# with_solar.net
KiCad netlist of a schematic drawn in EAGLE
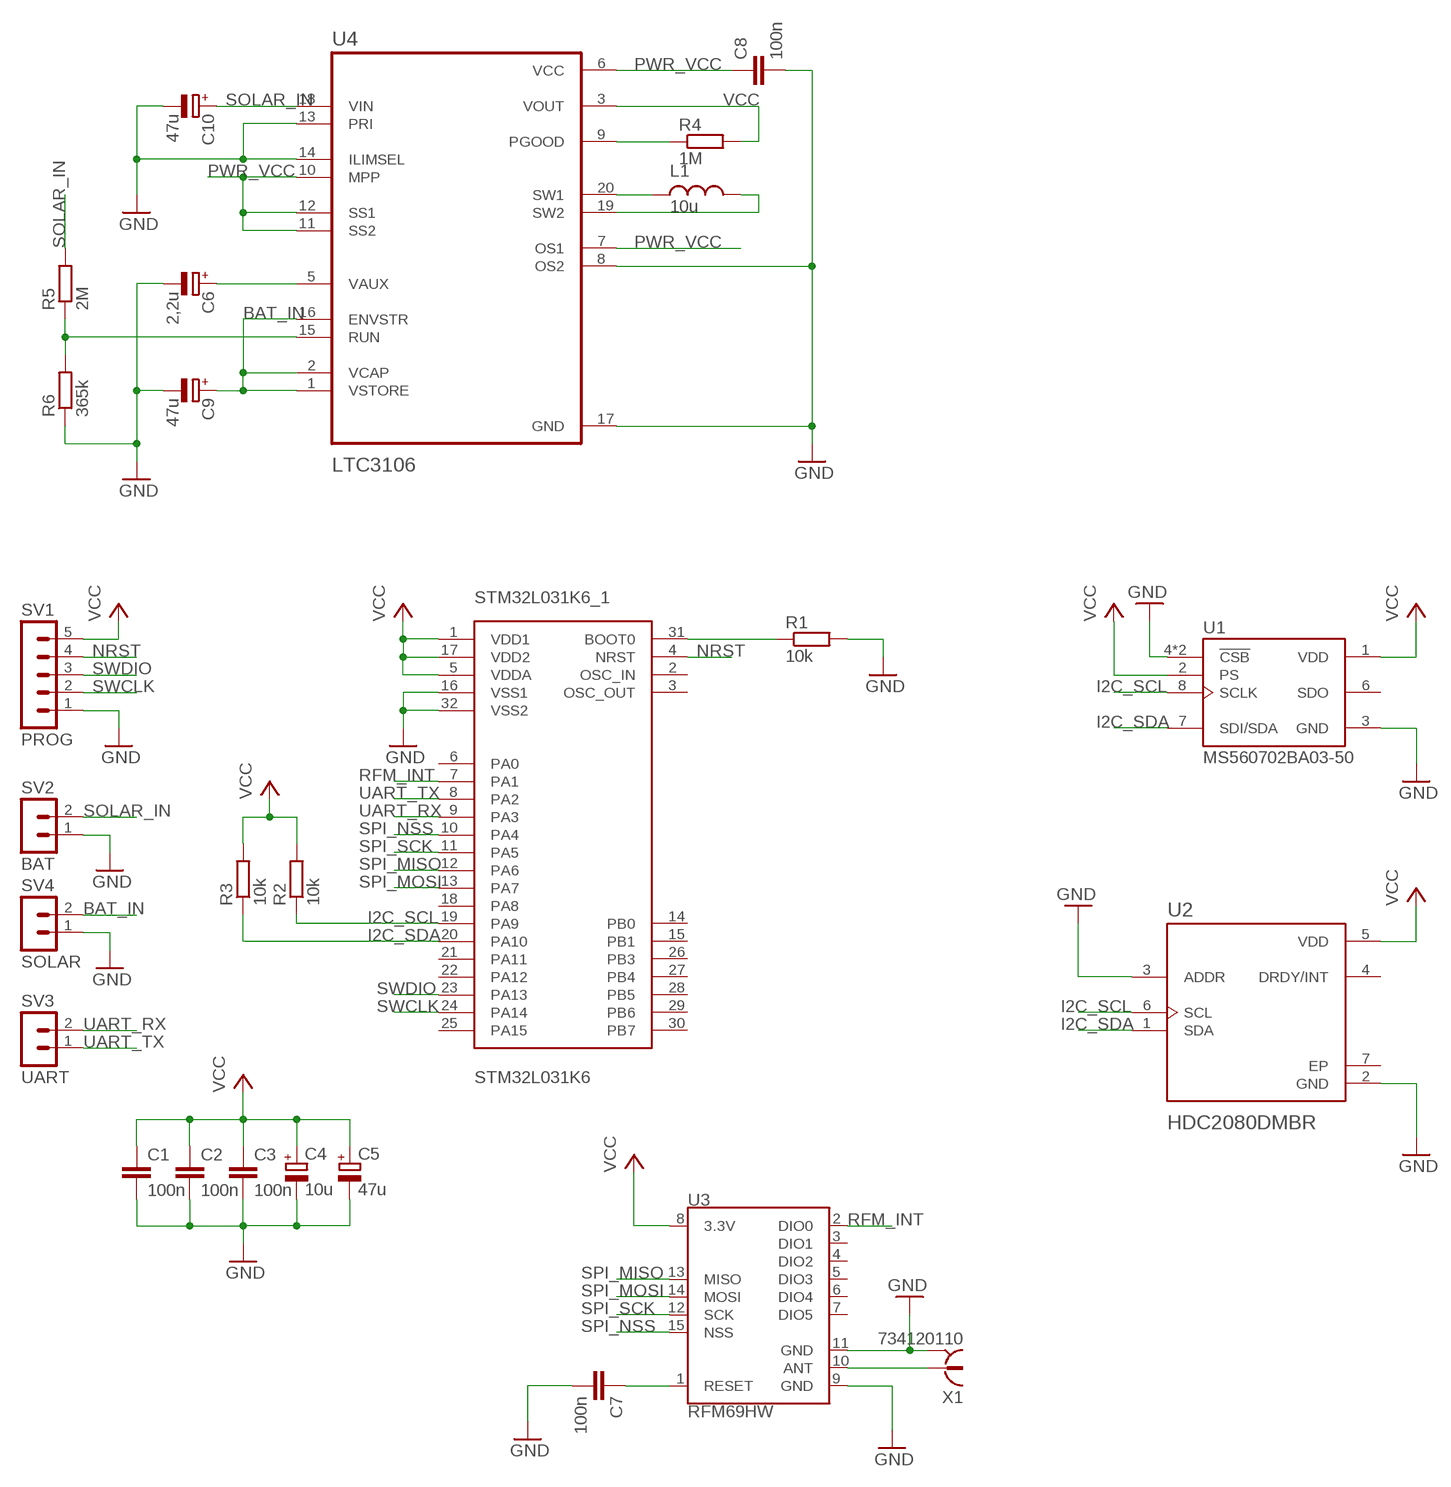
[diagram p0: schematic, sheet 1]

(export (version "E")
  (design (tool "Eeschema 10.0.6"))
  (components
    (comp (ref "C1")
      (value "100n")
      (footprint "eagle-import:C1206")
      (libsource (lib "eagle-import") (part "C-EUC1206"))
    )
    (comp (ref "C2")
      (value "100n")
      (footprint "eagle-import:C1206")
      (libsource (lib "eagle-import") (part "C-EUC1206"))
    )
    (comp (ref "C3")
      (value "100n")
      (footprint "eagle-import:C1206")
      (libsource (lib "eagle-import") (part "C-EUC1206"))
    )
    (comp (ref "C4")
      (value "10u")
      (footprint "eagle-import:UD-4X5,8_NICHICON")
      (libsource (lib "eagle-import") (part "CPOL-EUUD-4X5,8"))
    )
    (comp (ref "C5")
      (value "47u")
      (footprint "eagle-import:UD-4X5,8_NICHICON")
      (libsource (lib "eagle-import") (part "CPOL-EUUD-4X5,8"))
    )
    (comp (ref "C6")
      (value "2,2u")
      (footprint "eagle-import:UD-4X5,8_NICHICON")
      (libsource (lib "eagle-import") (part "CPOL-EUUD-4X5,8"))
    )
    (comp (ref "C7")
      (value "100n")
      (footprint "eagle-import:C1206")
      (libsource (lib "eagle-import") (part "C-EUC1206"))
    )
    (comp (ref "C8")
      (value "100n")
      (footprint "eagle-import:C1206")
      (libsource (lib "eagle-import") (part "C-EUC1206"))
    )
    (comp (ref "C9")
      (value "47u")
      (footprint "eagle-import:UD-4X5,8_NICHICON")
      (libsource (lib "eagle-import") (part "CPOL-EUUD-4X5,8"))
    )
    (comp (ref "C10")
      (value "47u")
      (footprint "eagle-import:UD-4X5,8_NICHICON")
      (libsource (lib "eagle-import") (part "CPOL-EUUD-4X5,8"))
    )
    (comp (ref "L1")
      (value "10u")
      (footprint "eagle-import:R1210")
      (libsource (lib "eagle-import") (part "L1210"))
    )
    (comp (ref "R1")
      (value "10k")
      (footprint "eagle-import:R0805")
      (libsource (lib "eagle-import") (part "R-EU_R0805"))
    )
    (comp (ref "R2")
      (value "10k")
      (footprint "eagle-import:R0805")
      (libsource (lib "eagle-import") (part "R-EU_R0805"))
    )
    (comp (ref "R3")
      (value "10k")
      (footprint "eagle-import:R0805")
      (libsource (lib "eagle-import") (part "R-EU_R0805"))
    )
    (comp (ref "R4")
      (value "1M")
      (footprint "eagle-import:R0805")
      (libsource (lib "eagle-import") (part "R-EU_R0805"))
    )
    (comp (ref "R5")
      (value "2M")
      (footprint "eagle-import:R0805")
      (libsource (lib "eagle-import") (part "R-EU_R0805"))
    )
    (comp (ref "R6")
      (value "365k")
      (footprint "eagle-import:R0805")
      (libsource (lib "eagle-import") (part "R-EU_R0805"))
    )
    (comp (ref "STM32L031K6_1")
      (value "STM32L031K6")
      (footprint "eagle-import:LQFP32-7X7")
      (libsource (lib "eagle-import") (part "STM32L031K6"))
    )
    (comp (ref "SV1")
      (value "PROG")
      (footprint "eagle-import:MA05-1")
      (libsource (lib "eagle-import") (part "MA05-1"))
    )
    (comp (ref "SV2")
      (value "BAT")
      (footprint "eagle-import:MA02-1")
      (libsource (lib "eagle-import") (part "MA02-1"))
    )
    (comp (ref "SV3")
      (value "UART")
      (footprint "eagle-import:MA02-1")
      (libsource (lib "eagle-import") (part "MA02-1"))
    )
    (comp (ref "SV4")
      (value "SOLAR")
      (footprint "eagle-import:MA02-1")
      (libsource (lib "eagle-import") (part "MA02-1"))
    )
    (comp (ref "U1")
      (value "MS560702BA03-50")
      (footprint "eagle-import:SON125P300X500X100-8N")
      (fields (field (name "MF") "TE Connectivity"))
      (libsource (lib "eagle-import") (part "MS560702BA03-50"))
    )
    (comp (ref "U2")
      (value "HDC2080DMBR")
      (footprint "eagle-import:SON100P300X300X80-7N")
      (fields (field (name "MF") "Texas Instruments"))
      (libsource (lib "eagle-import") (part "HDC2080DMBR"))
    )
    (comp (ref "U3")
      (value "RFM69HW")
      (footprint "eagle-import:RFM69W-XXXS2")
      (libsource (lib "eagle-import") (part "RFM69HW"))
    )
    (comp (ref "U4")
      (value "LTC3106")
      (footprint "eagle-import:LTC3106")
      (libsource (lib "eagle-import") (part "LTC3106"))
    )
    (comp (ref "X1")
      (value "734120110")
      (footprint "eagle-import:734120110")
      (libsource (lib "eagle-import") (part "734120110"))
    )
  )
  (nets
    (net (code "1") (name "/BAT_IN") (class "Default")
      (node (ref "C9") (pin "+") (pinfunction "+_+") (pintype "passive"))
      (node (ref "SV4") (pin "2") (pinfunction "3_2") (pintype "passive"))
      (node (ref "U4") (pin "1") (pinfunction "VSTORE_1") (pintype "bidirectional"))
      (node (ref "U4") (pin "16") (pinfunction "ENVSTR_16") (pintype "input"))
      (node (ref "U4") (pin "2") (pinfunction "VCAP_2") (pintype "bidirectional"))
    )
    (net (code "2") (name "/I2C_SCL") (class "Default")
      (node (ref "R2") (pin "1") (pinfunction "1_1") (pintype "passive"))
      (node (ref "STM32L031K6_1") (pin "19") (pinfunction "PA9_19") (pintype "bidirectional"))
      (node (ref "U1") (pin "8") (pinfunction "SCLK_8") (pintype "input"))
      (node (ref "U2") (pin "6") (pinfunction "SCL_6") (pintype "input"))
    )
    (net (code "3") (name "/I2C_SDA") (class "Default")
      (node (ref "R3") (pin "1") (pinfunction "1_1") (pintype "passive"))
      (node (ref "STM32L031K6_1") (pin "20") (pinfunction "PA10_20") (pintype "bidirectional"))
      (node (ref "U1") (pin "7") (pinfunction "SDI/SDA_7") (pintype "bidirectional"))
      (node (ref "U2") (pin "1") (pinfunction "SDA_1") (pintype "bidirectional"))
    )
    (net (code "4") (name "/NRST") (class "Default")
      (node (ref "STM32L031K6_1") (pin "4") (pinfunction "NRST_4") (pintype "bidirectional"))
      (node (ref "SV1") (pin "4") (pinfunction "4_4") (pintype "passive"))
    )
    (net (code "5") (name "/PWR_VCC") (class "Default")
      (node (ref "C8") (pin "1") (pinfunction "1_1") (pintype "passive"))
      (node (ref "U4") (pin "10") (pinfunction "MPP_10") (pintype "input"))
      (node (ref "U4") (pin "11") (pinfunction "SS2_11") (pintype "input"))
      (node (ref "U4") (pin "12") (pinfunction "SS1_12") (pintype "input"))
      (node (ref "U4") (pin "6") (pinfunction "VCC_6") (pintype "power_in"))
      (node (ref "U4") (pin "7") (pinfunction "OS1_7") (pintype "input"))
    )
    (net (code "6") (name "/RFM_INT") (class "Default")
      (node (ref "STM32L031K6_1") (pin "7") (pinfunction "PA1_7") (pintype "bidirectional"))
      (node (ref "U3") (pin "2") (pinfunction "DIO0_2") (pintype "bidirectional"))
    )
    (net (code "7") (name "/SOLAR_IN") (class "Default")
      (node (ref "C10") (pin "+") (pinfunction "+_+") (pintype "passive"))
      (node (ref "R5") (pin "2") (pinfunction "2_2") (pintype "passive"))
      (node (ref "SV2") (pin "2") (pinfunction "3_2") (pintype "passive"))
      (node (ref "U4") (pin "18") (pinfunction "VIN_18") (pintype "input"))
    )
    (net (code "8") (name "/SPI_MISO") (class "Default")
      (node (ref "STM32L031K6_1") (pin "12") (pinfunction "PA6_12") (pintype "bidirectional"))
      (node (ref "U3") (pin "13") (pinfunction "MISO_13") (pintype "bidirectional"))
    )
    (net (code "9") (name "/SPI_MOSI") (class "Default")
      (node (ref "STM32L031K6_1") (pin "13") (pinfunction "PA7_13") (pintype "bidirectional"))
      (node (ref "U3") (pin "14") (pinfunction "MOSI_14") (pintype "input"))
    )
    (net (code "10") (name "/SPI_NSS") (class "Default")
      (node (ref "STM32L031K6_1") (pin "10") (pinfunction "PA4_10") (pintype "bidirectional"))
      (node (ref "U3") (pin "15") (pinfunction "NSS_15") (pintype "input"))
    )
    (net (code "11") (name "/SPI_SCK") (class "Default")
      (node (ref "STM32L031K6_1") (pin "11") (pinfunction "PA5_11") (pintype "bidirectional"))
      (node (ref "U3") (pin "12") (pinfunction "SCK_12") (pintype "input"))
    )
    (net (code "12") (name "/SWCLK") (class "Default")
      (node (ref "STM32L031K6_1") (pin "24") (pinfunction "PA14_24") (pintype "bidirectional"))
      (node (ref "SV1") (pin "2") (pinfunction "2_2") (pintype "passive"))
    )
    (net (code "13") (name "/SWDIO") (class "Default")
      (node (ref "STM32L031K6_1") (pin "23") (pinfunction "PA13_23") (pintype "bidirectional"))
      (node (ref "SV1") (pin "3") (pinfunction "3_3") (pintype "passive"))
    )
    (net (code "14") (name "/UART_RX") (class "Default")
      (node (ref "STM32L031K6_1") (pin "9") (pinfunction "PA3_9") (pintype "bidirectional"))
      (node (ref "SV3") (pin "2") (pinfunction "3_2") (pintype "passive"))
    )
    (net (code "15") (name "/UART_TX") (class "Default")
      (node (ref "STM32L031K6_1") (pin "8") (pinfunction "PA2_8") (pintype "bidirectional"))
      (node (ref "SV3") (pin "1") (pinfunction "2_1") (pintype "passive"))
    )
    (net (code "16") (name "GND") (class "Default")
      (node (ref "C1") (pin "2") (pinfunction "2_2") (pintype "passive"))
      (node (ref "C10") (pin "-") (pinfunction "-_-") (pintype "passive"))
      (node (ref "C2") (pin "2") (pinfunction "2_2") (pintype "passive"))
      (node (ref "C3") (pin "2") (pinfunction "2_2") (pintype "passive"))
      (node (ref "C4") (pin "-") (pinfunction "-_-") (pintype "passive"))
      (node (ref "C5") (pin "-") (pinfunction "-_-") (pintype "passive"))
      (node (ref "C6") (pin "-") (pinfunction "-_-") (pintype "passive"))
      (node (ref "C7") (pin "2") (pinfunction "2_2") (pintype "passive"))
      (node (ref "C8") (pin "2") (pinfunction "2_2") (pintype "passive"))
      (node (ref "C9") (pin "-") (pinfunction "-_-") (pintype "passive"))
      (node (ref "R1") (pin "2") (pinfunction "2_2") (pintype "passive"))
      (node (ref "R6") (pin "1") (pinfunction "1_1") (pintype "passive"))
      (node (ref "STM32L031K6_1") (pin "16") (pinfunction "VSS1_16") (pintype "bidirectional"))
      (node (ref "STM32L031K6_1") (pin "32") (pinfunction "VSS2_32") (pintype "bidirectional"))
      (node (ref "SV1") (pin "1") (pinfunction "1_1") (pintype "passive"))
      (node (ref "SV2") (pin "1") (pinfunction "2_1") (pintype "passive"))
      (node (ref "SV4") (pin "1") (pinfunction "2_1") (pintype "passive"))
      (node (ref "U1") (pin "3") (pinfunction "GND_3") (pintype "power_in"))
      (node (ref "U1") (pin "4") (pinfunction "~{CSB}_4") (pintype "input"))
      (node (ref "U1") (pin "5") (pinfunction "~{CSB}_5") (pintype "input"))
      (node (ref "U2") (pin "2") (pinfunction "GND_2") (pintype "power_in"))
      (node (ref "U2") (pin "3") (pinfunction "ADDR_3") (pintype "input"))
      (node (ref "U3") (pin "11") (pinfunction "GND_11") (pintype "power_in"))
      (node (ref "U3") (pin "9") (pinfunction "GND_9") (pintype "power_in"))
      (node (ref "U4") (pin "13") (pinfunction "PRI_13") (pintype "input"))
      (node (ref "U4") (pin "14") (pinfunction "ILIMSEL_14") (pintype "input"))
      (node (ref "U4") (pin "17") (pinfunction "GND_17") (pintype "power_in"))
      (node (ref "U4") (pin "8") (pinfunction "OS2_8") (pintype "input"))
      (node (ref "X1") (pin "S@1") (pinfunction "2_S@1") (pintype "passive"))
      (node (ref "X1") (pin "S@2") (pinfunction "2_S@2") (pintype "passive"))
      (node (ref "X1") (pin "S@3") (pinfunction "2_S@3") (pintype "passive"))
    )
    (net (code "17") (name "Net-(STM32L031K6_1-BOOT0)") (class "Default")
      (node (ref "R1") (pin "1") (pinfunction "1_1") (pintype "passive"))
      (node (ref "STM32L031K6_1") (pin "31") (pinfunction "BOOT0_31") (pintype "bidirectional"))
    )
    (net (code "18") (name "Net-(U3-ANT)") (class "Default")
      (node (ref "U3") (pin "10") (pinfunction "ANT_10") (pintype "passive"))
      (node (ref "X1") (pin "1") (pinfunction "1_1") (pintype "passive"))
    )
    (net (code "19") (name "Net-(U3-RESET)") (class "Default")
      (node (ref "C7") (pin "1") (pinfunction "1_1") (pintype "passive"))
      (node (ref "U3") (pin "1") (pinfunction "RESET_1") (pintype "input"))
    )
    (net (code "20") (name "Net-(U4-PGOOD)") (class "Default")
      (node (ref "R4") (pin "1") (pinfunction "1_1") (pintype "passive"))
      (node (ref "U4") (pin "9") (pinfunction "PGOOD_9") (pintype "bidirectional"))
    )
    (net (code "21") (name "Net-(U4-RUN)") (class "Default")
      (node (ref "R5") (pin "1") (pinfunction "1_1") (pintype "passive"))
      (node (ref "R6") (pin "2") (pinfunction "2_2") (pintype "passive"))
      (node (ref "U4") (pin "15") (pinfunction "RUN_15") (pintype "input"))
    )
    (net (code "22") (name "Net-(U4-SW1)") (class "Default")
      (node (ref "L1") (pin "1") (pinfunction "1_1") (pintype "passive"))
      (node (ref "U4") (pin "20") (pinfunction "SW1_20") (pintype "bidirectional"))
    )
    (net (code "23") (name "Net-(U4-SW2)") (class "Default")
      (node (ref "L1") (pin "2") (pinfunction "2_2") (pintype "passive"))
      (node (ref "U4") (pin "19") (pinfunction "SW2_19") (pintype "bidirectional"))
    )
    (net (code "24") (name "Net-(U4-VAUX)") (class "Default")
      (node (ref "C6") (pin "+") (pinfunction "+_+") (pintype "passive"))
      (node (ref "U4") (pin "5") (pinfunction "VAUX_5") (pintype "bidirectional"))
    )
    (net (code "25") (name "VCC") (class "Default")
      (node (ref "C1") (pin "1") (pinfunction "1_1") (pintype "passive"))
      (node (ref "C2") (pin "1") (pinfunction "1_1") (pintype "passive"))
      (node (ref "C3") (pin "1") (pinfunction "1_1") (pintype "passive"))
      (node (ref "C4") (pin "+") (pinfunction "+_+") (pintype "passive"))
      (node (ref "C5") (pin "+") (pinfunction "+_+") (pintype "passive"))
      (node (ref "R2") (pin "2") (pinfunction "2_2") (pintype "passive"))
      (node (ref "R3") (pin "2") (pinfunction "2_2") (pintype "passive"))
      (node (ref "R4") (pin "2") (pinfunction "2_2") (pintype "passive"))
      (node (ref "STM32L031K6_1") (pin "1") (pinfunction "VDD1_1") (pintype "bidirectional"))
      (node (ref "STM32L031K6_1") (pin "17") (pinfunction "VDD2_17") (pintype "bidirectional"))
      (node (ref "STM32L031K6_1") (pin "5") (pinfunction "VDDA_5") (pintype "bidirectional"))
      (node (ref "SV1") (pin "5") (pinfunction "5_5") (pintype "passive"))
      (node (ref "U1") (pin "1") (pinfunction "VDD_1") (pintype "power_in"))
      (node (ref "U1") (pin "2") (pinfunction "PS_2") (pintype "input"))
      (node (ref "U2") (pin "5") (pinfunction "VDD_5") (pintype "power_in"))
      (node (ref "U3") (pin "8") (pinfunction "3.3V_8") (pintype "power_in"))
      (node (ref "U4") (pin "3") (pinfunction "VOUT_3") (pintype "output"))
    )
    (net (code "26") (name "unconnected-(STM32L031K6_1-OSC_IN-Pad2)") (class "Default")
      (node (ref "STM32L031K6_1") (pin "2") (pinfunction "OSC_IN_2") (pintype "bidirectional"))
    )
    (net (code "27") (name "unconnected-(STM32L031K6_1-OSC_OUT-Pad3)") (class "Default")
      (node (ref "STM32L031K6_1") (pin "3") (pinfunction "OSC_OUT_3") (pintype "bidirectional"))
    )
    (net (code "28") (name "unconnected-(STM32L031K6_1-PA0-Pad6)") (class "Default")
      (node (ref "STM32L031K6_1") (pin "6") (pinfunction "PA0_6") (pintype "bidirectional"))
    )
    (net (code "29") (name "unconnected-(STM32L031K6_1-PA8-Pad18)") (class "Default")
      (node (ref "STM32L031K6_1") (pin "18") (pinfunction "PA8_18") (pintype "bidirectional"))
    )
    (net (code "30") (name "unconnected-(STM32L031K6_1-PA11-Pad21)") (class "Default")
      (node (ref "STM32L031K6_1") (pin "21") (pinfunction "PA11_21") (pintype "bidirectional"))
    )
    (net (code "31") (name "unconnected-(STM32L031K6_1-PA12-Pad22)") (class "Default")
      (node (ref "STM32L031K6_1") (pin "22") (pinfunction "PA12_22") (pintype "bidirectional"))
    )
    (net (code "32") (name "unconnected-(STM32L031K6_1-PA15-Pad25)") (class "Default")
      (node (ref "STM32L031K6_1") (pin "25") (pinfunction "PA15_25") (pintype "bidirectional"))
    )
    (net (code "33") (name "unconnected-(STM32L031K6_1-PB0-Pad14)") (class "Default")
      (node (ref "STM32L031K6_1") (pin "14") (pinfunction "PB0_14") (pintype "bidirectional"))
    )
    (net (code "34") (name "unconnected-(STM32L031K6_1-PB1-Pad15)") (class "Default")
      (node (ref "STM32L031K6_1") (pin "15") (pinfunction "PB1_15") (pintype "bidirectional"))
    )
    (net (code "35") (name "unconnected-(STM32L031K6_1-PB3-Pad26)") (class "Default")
      (node (ref "STM32L031K6_1") (pin "26") (pinfunction "PB3_26") (pintype "bidirectional"))
    )
    (net (code "36") (name "unconnected-(STM32L031K6_1-PB4-Pad27)") (class "Default")
      (node (ref "STM32L031K6_1") (pin "27") (pinfunction "PB4_27") (pintype "bidirectional"))
    )
    (net (code "37") (name "unconnected-(STM32L031K6_1-PB5-Pad28)") (class "Default")
      (node (ref "STM32L031K6_1") (pin "28") (pinfunction "PB5_28") (pintype "bidirectional"))
    )
    (net (code "38") (name "unconnected-(STM32L031K6_1-PB6-Pad29)") (class "Default")
      (node (ref "STM32L031K6_1") (pin "29") (pinfunction "PB6_29") (pintype "bidirectional"))
    )
    (net (code "39") (name "unconnected-(STM32L031K6_1-PB7-Pad30)") (class "Default")
      (node (ref "STM32L031K6_1") (pin "30") (pinfunction "PB7_30") (pintype "bidirectional"))
    )
    (net (code "40") (name "unconnected-(U1-SDO-Pad6)") (class "Default")
      (node (ref "U1") (pin "6") (pinfunction "SDO_6") (pintype "output"))
    )
    (net (code "41") (name "unconnected-(U2-DRDY{slash}INT-Pad4)") (class "Default")
      (node (ref "U2") (pin "4") (pinfunction "DRDY/INT_4") (pintype "output"))
    )
    (net (code "42") (name "unconnected-(U2-EP-Pad7)") (class "Default")
      (node (ref "U2") (pin "7") (pinfunction "EP_7") (pintype "passive"))
    )
    (net (code "43") (name "unconnected-(U3-DIO1-Pad3)") (class "Default")
      (node (ref "U3") (pin "3") (pinfunction "DIO1_3") (pintype "bidirectional"))
    )
    (net (code "44") (name "unconnected-(U3-DIO2-Pad4)") (class "Default")
      (node (ref "U3") (pin "4") (pinfunction "DIO2_4") (pintype "bidirectional"))
    )
    (net (code "45") (name "unconnected-(U3-DIO3-Pad5)") (class "Default")
      (node (ref "U3") (pin "5") (pinfunction "DIO3_5") (pintype "bidirectional"))
    )
    (net (code "46") (name "unconnected-(U3-DIO4-Pad6)") (class "Default")
      (node (ref "U3") (pin "6") (pinfunction "DIO4_6") (pintype "bidirectional"))
    )
    (net (code "47") (name "unconnected-(U3-DIO5-Pad7)") (class "Default")
      (node (ref "U3") (pin "7") (pinfunction "DIO5_7") (pintype "bidirectional"))
    )
  )
)
